# 12mm_rotary_knob.net
KiCad netlist of a schematic drawn in Altium Designer
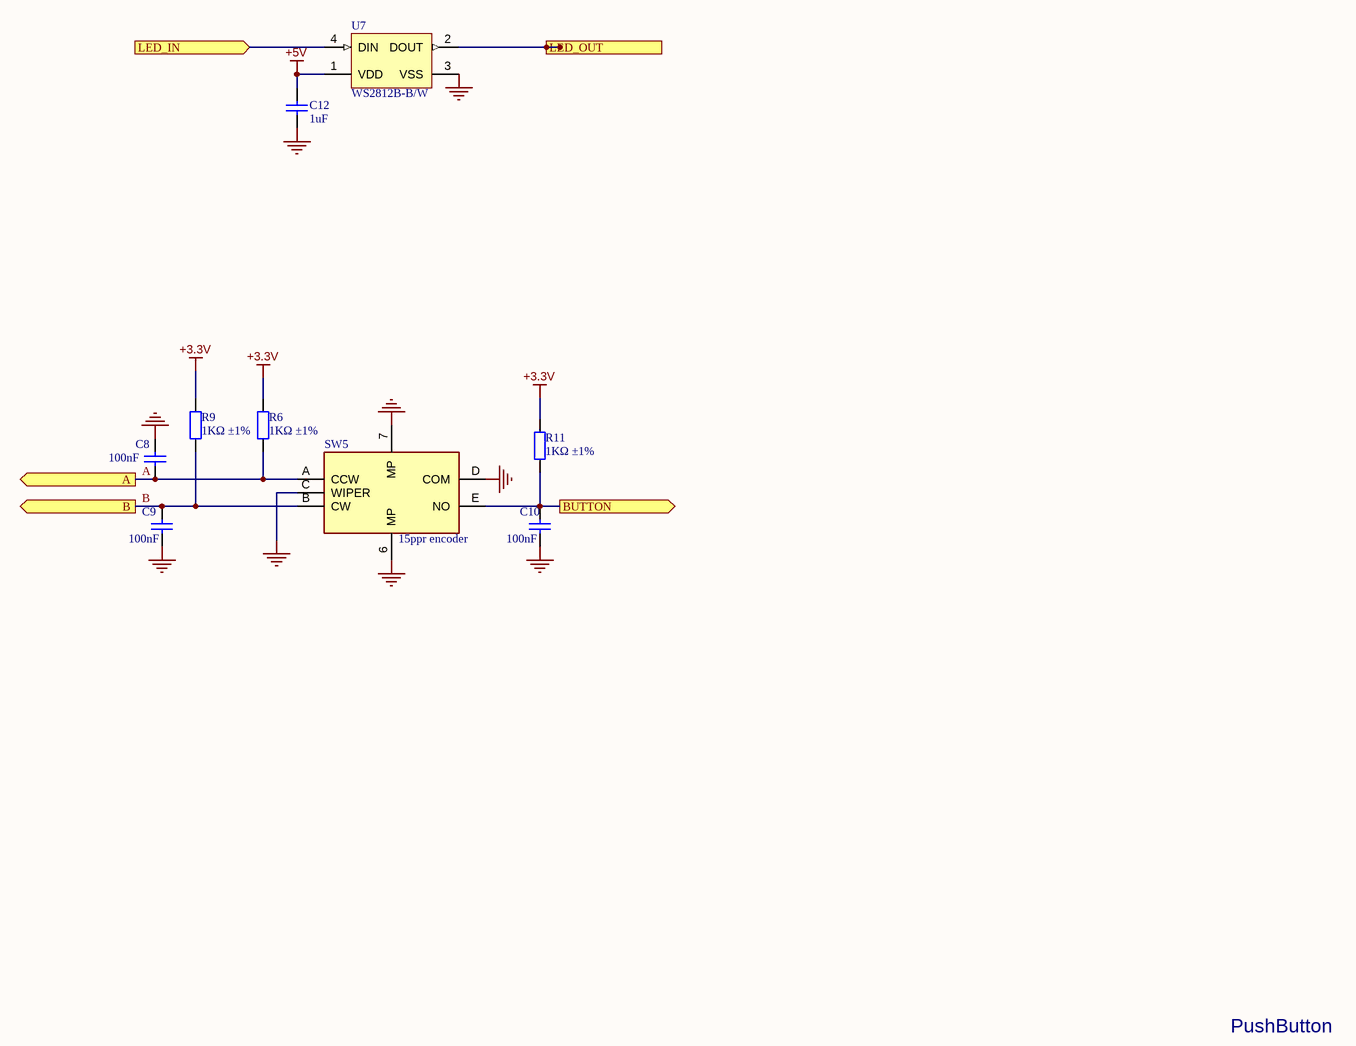
[diagram p0: 12mm_rotary_knob.SchDoc]

(export (version "E")
  (design (tool "Eeschema 10.0.6"))
  (components
    (comp (ref "C8")
      (value "100nF")
      (footprint "0603_C")
      (description "Chip capacitors")
      (fields (field (name "MANUFACTURER") "YAGEO") (field (name "PARTNUMBER") "CC0603KRX7R9BB104"))
      (libsource (lib "Cap") (part "0603 100nF (104) 10% 50V"))
    )
    (comp (ref "C9")
      (value "100nF")
      (footprint "0603_C")
      (description "Chip capacitors")
      (fields (field (name "MANUFACTURER") "YAGEO") (field (name "PARTNUMBER") "CC0603KRX7R9BB104"))
      (libsource (lib "Cap") (part "0603 100nF (104) 10% 50V"))
    )
    (comp (ref "C10")
      (value "100nF")
      (footprint "0603_C")
      (description "Chip capacitors")
      (fields (field (name "MANUFACTURER") "YAGEO") (field (name "PARTNUMBER") "CC0603KRX7R9BB104"))
      (libsource (lib "Cap") (part "0603 100nF (104) 10% 50V"))
    )
    (comp (ref "C12")
      (value "1uF")
      (footprint "0603_C")
      (description "Chip capacitors")
      (fields
        (field (name "MANUFACTURER") "Samsung Electro-Mechanics")
        (field (name "PARTNUMBER") "CL10A105KB8NNNC")
      )
      (libsource (lib "Cap") (part "0603 1uF (105) 10% 50V"))
    )
    (comp (ref "R6")
      (value "1KΩ ±1%")
      (footprint "0603_R")
      (description "Chip resistor")
      (fields (field (name "MANUFACTURER") "Uniroyal Elec") (field (name "PARTNUMBER") "0603WAF1001T5E"))
      (libsource (lib "RES") (part "0603 1K (1001) 1%"))
    )
    (comp (ref "R9")
      (value "1KΩ ±1%")
      (footprint "0603_R")
      (description "Chip resistor")
      (fields (field (name "MANUFACTURER") "Uniroyal Elec") (field (name "PARTNUMBER") "0603WAF1001T5E"))
      (libsource (lib "RES") (part "0603 1K (1001) 1%"))
    )
    (comp (ref "R11")
      (value "1KΩ ±1%")
      (footprint "0603_R")
      (description "Chip resistor")
      (fields (field (name "MANUFACTURER") "Uniroyal Elec") (field (name "PARTNUMBER") "0603WAF1001T5E"))
      (libsource (lib "RES") (part "0603 1K (1001) 1%"))
    )
    (comp (ref "SW5")
      (value "15ppr encoder")
      (footprint "Universal_breakout:SW-TH_EC11E15244G1")
      (description "Plugin Rotary Encoders ROHS 11mm")
      (fields (field (name "MANUFACTURER_PART_NUMBER") "EC11E15244G1"))
      (libsource (lib "I2C_Jog_Controller") (part "EC11E15244G1"))
    )
    (comp (ref "U7")
      (value "WS2812B-B/W")
      (footprint "ADA-RGB-1655_V")
      (fields (field (name "MANUFACTURER") "Worldsemi"))
      (libsource (lib "Altium Content Vault") (part "ADA-RGB-1655-4"))
    )
  )
  (nets
    (net (code "1") (name "+3.3V") (class "Default")
      (node (ref "R11") (pin "1") (pinfunction "1_1") (pintype "passive"))
      (node (ref "R6") (pin "1") (pinfunction "1_1") (pintype "passive"))
      (node (ref "R9") (pin "1") (pinfunction "1_1") (pintype "passive"))
    )
    (net (code "2") (name "+5V") (class "Default")
      (node (ref "C12") (pin "2") (pinfunction "2_2") (pintype "passive"))
      (node (ref "U7") (pin "1") (pinfunction "VDD_1") (pintype "power_in"))
    )
    (net (code "3") (name "/A") (class "Default")
      (node (ref "C8") (pin "1") (pinfunction "1_1") (pintype "passive"))
      (node (ref "R6") (pin "2") (pinfunction "2_2") (pintype "passive"))
      (node (ref "SW5") (pin "A") (pinfunction "CCW_A") (pintype "passive"))
    )
    (net (code "4") (name "/B") (class "Default")
      (node (ref "C9") (pin "2") (pinfunction "2_2") (pintype "passive"))
      (node (ref "R9") (pin "2") (pinfunction "2_2") (pintype "passive"))
      (node (ref "SW5") (pin "B") (pinfunction "CW_B") (pintype "passive"))
    )
    (net (code "5") (name "/BUTTON") (class "Default")
      (node (ref "C10") (pin "2") (pinfunction "2_2") (pintype "passive"))
      (node (ref "R11") (pin "2") (pinfunction "2_2") (pintype "passive"))
      (node (ref "SW5") (pin "E") (pinfunction "NO_E") (pintype "passive"))
    )
    (net (code "6") (name "/LED_IN") (class "Default")
      (node (ref "U7") (pin "4") (pinfunction "DIN_4") (pintype "input"))
    )
    (net (code "7") (name "/LED_OUT") (class "Default")
      (node (ref "U7") (pin "2") (pinfunction "DOUT_2") (pintype "output"))
    )
    (net (code "8") (name "GND") (class "Default")
      (node (ref "C10") (pin "1") (pinfunction "1_1") (pintype "passive"))
      (node (ref "C12") (pin "1") (pinfunction "1_1") (pintype "passive"))
      (node (ref "C8") (pin "2") (pinfunction "2_2") (pintype "passive"))
      (node (ref "C9") (pin "1") (pinfunction "1_1") (pintype "passive"))
      (node (ref "SW5") (pin "6") (pinfunction "MP_6") (pintype "passive"))
      (node (ref "SW5") (pin "7") (pinfunction "MP_7") (pintype "passive"))
      (node (ref "SW5") (pin "C") (pinfunction "WIPER_C") (pintype "passive"))
      (node (ref "SW5") (pin "D") (pinfunction "COM_D") (pintype "passive"))
      (node (ref "U7") (pin "3") (pinfunction "VSS_3") (pintype "power_in"))
    )
  )
)
